# main.net
KiCad netlist of a schematic drawn in Altium Designer
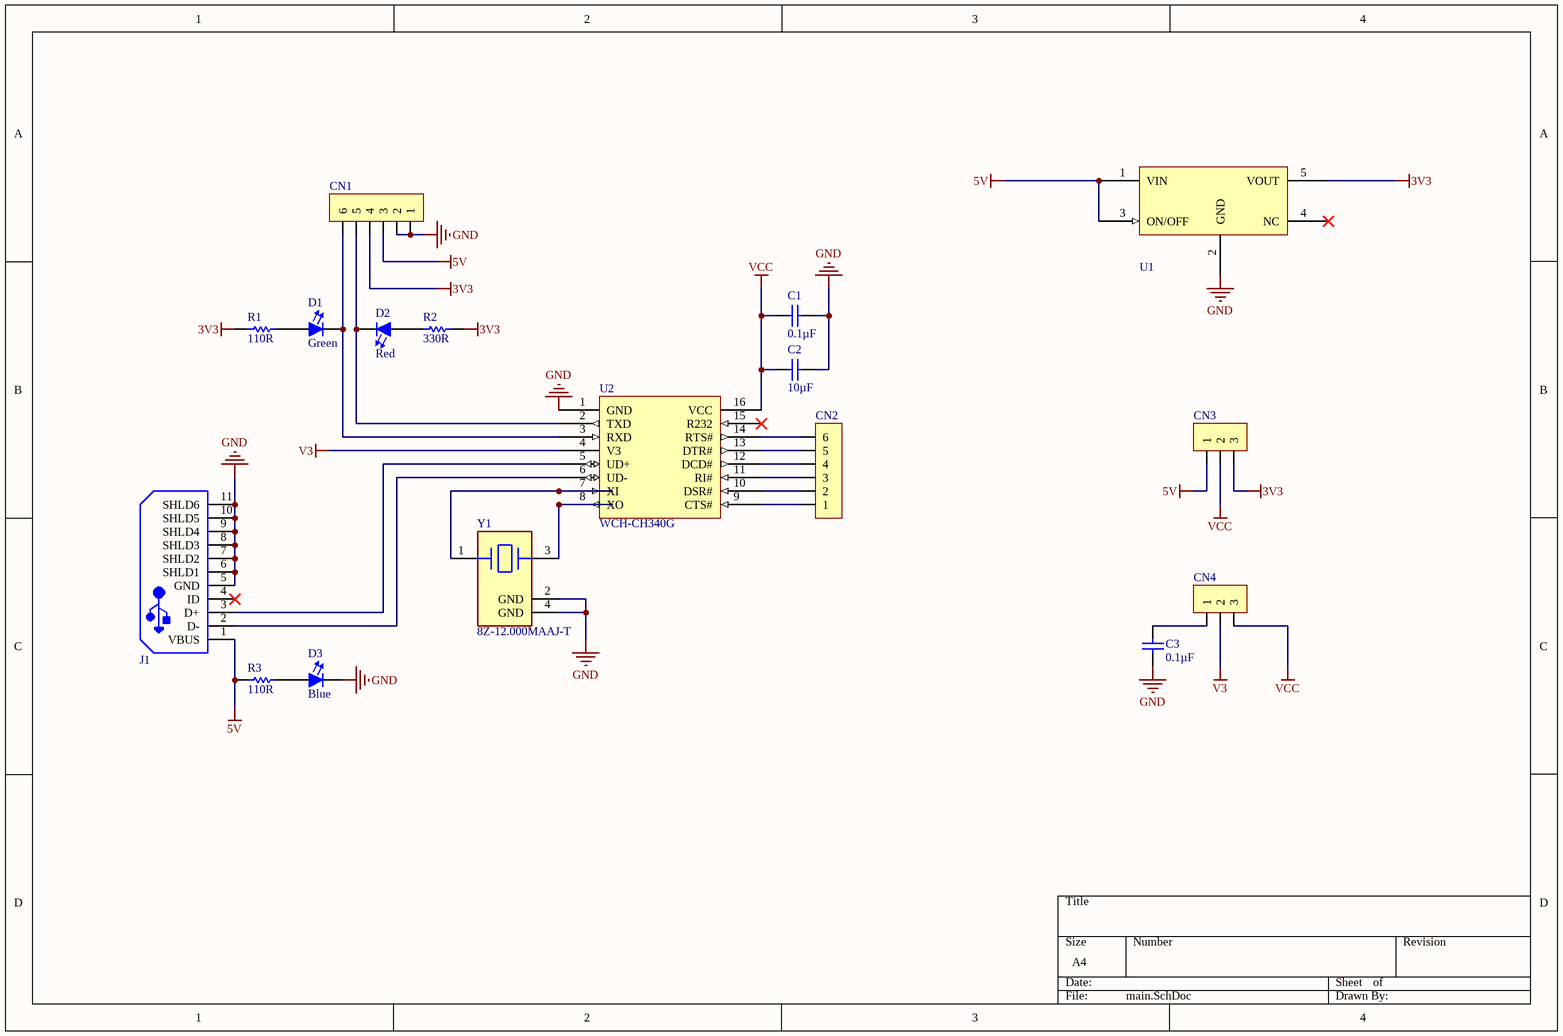
[diagram p0: main.SchDoc]

(export (version "E")
  (design (tool "Eeschema 10.0.6"))
  (components
    (comp (ref "C1")
      (value "0.1µF")
      (footprint "CAPC1608N(0603\")")
      (description "Capacitor, Ceramic, 16V, +/- 10%, 0603 SMD, X7R")
      (fields
        (field (name "Comment") "0.1uF 16V 0603 SMD, Ceramic")
        (field (name "CREATED BY") "Andy Bates")
        (field (name "SOURCE") "AUVic_Schematic_Library_Capacitors.SchLib")
        (field (name "PUBLISHER") "AUVic")
      )
      (libsource (lib "") (part "Symbol_1"))
    )
    (comp (ref "C2")
      (value "10µF")
      (footprint "CAPC1608N(0603\")")
      (description "Capacitor, Ceramic, 16V, +/- 10%, 0603 SMD, X7R")
      (fields
        (field (name "Comment") "0.1uF 16V 0603 SMD, Ceramic")
        (field (name "CREATED BY") "Andy Bates")
        (field (name "SOURCE") "AUVic_Schematic_Library_Capacitors.SchLib")
        (field (name "PUBLISHER") "AUVic")
      )
      (libsource (lib "") (part "Symbol_1"))
    )
    (comp (ref "C3")
      (value "0.1µF")
      (footprint "CAPC1608N(0603\")")
      (description "Capacitor, Ceramic, 16V, +/- 10%, 0603 SMD, X7R")
      (fields
        (field (name "Comment") "0.1uF 16V 0603 SMD, Ceramic")
        (field (name "CREATED BY") "Andy Bates")
        (field (name "SOURCE") "AUVic_Schematic_Library_Capacitors.SchLib")
        (field (name "PUBLISHER") "AUVic")
      )
      (libsource (lib "") (part "Symbol_1"))
    )
    (comp (ref "CN1")
      (value "Header, Male, 1x6")
      (footprint "Header, Male, 1X6")
      (description "1x6, Pads Pitch: 0.1\" (2.54mm), Through hole")
      (fields (field (name "SOURCE") "AUVic_Schematic_Library_Connectors.SchLib"))
      (libsource (lib "") (part "Symbol_3"))
    )
    (comp (ref "CN2")
      (value "Header, Male, 1x6")
      (footprint "Header, Male, 1X6")
      (description "1x6, Pads Pitch: 0.1\" (2.54mm), Through hole")
      (fields (field (name "SOURCE") "AUVic_Schematic_Library_Connectors.SchLib"))
      (libsource (lib "") (part "Symbol_4"))
    )
    (comp (ref "CN3")
      (value "Header, Male, 1x3, Pitch: 0.1\" (2.54mm), THT")
      (footprint "Header, Male, 1x3, Pitch: 0.1\" (2.54mm),THT")
      (fields
        (field (name "CREATED BY") "Ashwin Sira")
        (field (name "REVIEWED BY") "*")
        (field (name "SOURCE") "AUVic_Schematic_Library_Connectors.SchLib")
        (field (name "PUBLISHER") "AUVic")
      )
      (libsource (lib "") (part "Symbol_2"))
    )
    (comp (ref "CN4")
      (value "Header, Male, 1x3, Pitch: 0.1\" (2.54mm), THT")
      (footprint "Header, Male, 1x3, Pitch: 0.1\" (2.54mm),THT")
      (fields
        (field (name "CREATED BY") "Ashwin Sira")
        (field (name "REVIEWED BY") "*")
        (field (name "SOURCE") "AUVic_Schematic_Library_Connectors.SchLib")
        (field (name "PUBLISHER") "AUVic")
      )
      (libsource (lib "") (part "Symbol_2"))
    )
    (comp (ref "D1")
      (value "LT Q39G-Q1OO-25-1")
      (footprint "FP-LB_Q39E-MFG")
      (description "LED GREEN DIFFUSED 0603 SMD")
      (fields (field (name "COLOR") "Green"))
      (libsource (lib "AUVIC") (part "Symbol"))
    )
    (comp (ref "D2")
      (value "LSQ976-NR-1")
      (footprint "FP-LB_Q39E-MFG")
      (description "LED Red 645nm 2-Pin Chip 0603(1608Metric) T/R")
      (fields (field (name "COLOR") "Red"))
      (libsource (lib "AUVIC") (part "Symbol"))
    )
    (comp (ref "D3")
      (value "LBQ39E-N1OO-35-1")
      (footprint "FP-LB_Q39E-MFG")
      (description "LED BLUE DIFFUSED 0603 SMD")
      (fields (field (name "COLOR") "Blue"))
      (libsource (lib "AUVIC") (part "Symbol"))
    )
    (comp (ref "J1")
      (value "10118192-0002LF")
      (footprint "FCI-10118192-0001LF-5_V")
      (description "CONN RCPT USB2.0 MICRO B SMD R/A")
      (fields (field (name "DK PART NUMBER") "609-5379-1-ND"))
      (libsource (lib "AUVIC") (part "USB-5-6SHLD"))
    )
    (comp (ref "R1")
      (value "RC0603FR-07110RL")
      (footprint "RESC1608X55X25ML10T15")
      (description "RES SMD 110 OHM 1% 1/10W 0603")
      (fields (field (name "TOLERANCE") "1%") (field (name "RESISTANCE") "110R"))
      (libsource (lib "AUVIC") (part "RES"))
    )
    (comp (ref "R2")
      (value "RK73B1JTTD331J")
      (footprint "RESC1608X55X30LL20T10")
      (description "Res Thick Film 0603 330 Ohm 5% 0.1W(1/10W) ±200ppm/C Molded SMD Automotive T/R")
      (fields (field (name "TOLERANCE") "5%") (field (name "RESISTANCE") "330R"))
      (libsource (lib "AUVIC") (part "RES"))
    )
    (comp (ref "R3")
      (value "RC0603FR-07110RL")
      (footprint "RESC1608X55X25ML10T15")
      (description "RES SMD 110 OHM 1% 1/10W 0603")
      (fields (field (name "TOLERANCE") "1%") (field (name "RESISTANCE") "110R"))
      (libsource (lib "AUVIC") (part "RES"))
    )
    (comp (ref "U1")
      (value "LP2981-33DBVR")
      (footprint "SOT95P280X145-5N")
      (description "IC REG LINEAR 3.3V 100MA SOT23-5")
      (libsource (lib "AUVIC") (part "LP2981-33DBVR"))
    )
    (comp (ref "U2")
      (value "WCH-CH340G")
      (footprint "SOP127P600X175-16N")
      (description "USB to UART Transceiver. USB 2.0 2Mbps. LCSC #C14267")
      (fields (field (name "LCSC PART NUMBER") "C14267"))
      (libsource (lib "AUVIC") (part "WCH-CH340G"))
    )
    (comp (ref "Y1")
      (value "8Z-12.000MAAJ-T")
      (footprint "FP-8Z-MFG")
      (description "CRYSTAL 12.0000MHZ 18PF SMD")
      (fields (field (name "TOLERANCE") "30ppm"))
      (libsource (lib "Altium Content Vault") (part "82e0a36ce47690002882b131d1ef993"))
    )
  )
  (nets
    (net (code "1") (name "3V3") (class "Default")
      (node (ref "CN1") (pin "4") (pinfunction "4_4") (pintype "passive"))
      (node (ref "CN3") (pin "3") (pinfunction "3_3") (pintype "passive"))
      (node (ref "R1") (pin "2") (pinfunction "2_2") (pintype "passive"))
      (node (ref "R2") (pin "2") (pinfunction "2_2") (pintype "passive"))
      (node (ref "U1") (pin "5") (pinfunction "VOUT_5") (pintype "power_in"))
    )
    (net (code "2") (name "5V") (class "Default")
      (node (ref "CN1") (pin "3") (pinfunction "3_3") (pintype "passive"))
      (node (ref "CN3") (pin "1") (pinfunction "1_1") (pintype "passive"))
      (node (ref "J1") (pin "1") (pinfunction "VBUS_1") (pintype "passive"))
      (node (ref "R3") (pin "2") (pinfunction "2_2") (pintype "passive"))
      (node (ref "U1") (pin "1") (pinfunction "VIN_1") (pintype "power_in"))
      (node (ref "U1") (pin "3") (pinfunction "ON/OFF_3") (pintype "input"))
    )
    (net (code "3") (name "GND") (class "Default")
      (node (ref "C1") (pin "2") (pinfunction "Cathode_2") (pintype "passive"))
      (node (ref "C2") (pin "2") (pinfunction "Cathode_2") (pintype "passive"))
      (node (ref "C3") (pin "1") (pinfunction "Anode_1") (pintype "passive"))
      (node (ref "CN1") (pin "1") (pinfunction "1_1") (pintype "passive"))
      (node (ref "CN1") (pin "2") (pinfunction "2_2") (pintype "passive"))
      (node (ref "D3") (pin "1") (pinfunction "Cathode_1") (pintype "passive"))
      (node (ref "J1") (pin "10") (pinfunction "SHLD5_10") (pintype "passive"))
      (node (ref "J1") (pin "11") (pinfunction "SHLD6_11") (pintype "passive"))
      (node (ref "J1") (pin "5") (pinfunction "GND_5") (pintype "passive"))
      (node (ref "J1") (pin "6") (pinfunction "SHLD1_6") (pintype "passive"))
      (node (ref "J1") (pin "7") (pinfunction "SHLD2_7") (pintype "passive"))
      (node (ref "J1") (pin "8") (pinfunction "SHLD3_8") (pintype "passive"))
      (node (ref "J1") (pin "9") (pinfunction "SHLD4_9") (pintype "passive"))
      (node (ref "U1") (pin "2") (pinfunction "GND_2") (pintype "power_in"))
      (node (ref "U2") (pin "1") (pinfunction "GND_1") (pintype "power_in"))
      (node (ref "Y1") (pin "2") (pinfunction "GND_2") (pintype "power_in"))
      (node (ref "Y1") (pin "4") (pinfunction "GND_4") (pintype "power_in"))
    )
    (net (code "4") (name "Net-(C3-Cathode)") (class "Default")
      (node (ref "C3") (pin "2") (pinfunction "Cathode_2") (pintype "passive"))
      (node (ref "CN4") (pin "1") (pinfunction "1_1") (pintype "passive"))
    )
    (net (code "5") (name "Net-(D1-Anode)") (class "Default")
      (node (ref "D1") (pin "2") (pinfunction "Anode_2") (pintype "passive"))
      (node (ref "R1") (pin "1") (pinfunction "1_1") (pintype "passive"))
    )
    (net (code "6") (name "Net-(D1-Cathode)") (class "Default")
      (node (ref "CN1") (pin "6") (pinfunction "6_6") (pintype "passive"))
      (node (ref "D1") (pin "1") (pinfunction "Cathode_1") (pintype "passive"))
      (node (ref "U2") (pin "3") (pinfunction "RXD_3") (pintype "input"))
    )
    (net (code "7") (name "Net-(D2-Anode)") (class "Default")
      (node (ref "D2") (pin "2") (pinfunction "Anode_2") (pintype "passive"))
      (node (ref "R2") (pin "1") (pinfunction "1_1") (pintype "passive"))
    )
    (net (code "8") (name "Net-(D2-Cathode)") (class "Default")
      (node (ref "CN1") (pin "5") (pinfunction "5_5") (pintype "passive"))
      (node (ref "D2") (pin "1") (pinfunction "Cathode_1") (pintype "passive"))
      (node (ref "U2") (pin "2") (pinfunction "TXD_2") (pintype "output"))
    )
    (net (code "9") (name "Net-(D3-Anode)") (class "Default")
      (node (ref "D3") (pin "2") (pinfunction "Anode_2") (pintype "passive"))
      (node (ref "R3") (pin "1") (pinfunction "1_1") (pintype "passive"))
    )
    (net (code "10") (name "Net-(J1-D+)") (class "Default")
      (node (ref "J1") (pin "3") (pinfunction "D+_3") (pintype "passive"))
      (node (ref "U2") (pin "5") (pinfunction "UD+_5") (pintype "bidirectional"))
    )
    (net (code "11") (name "Net-(J1-D-)") (class "Default")
      (node (ref "J1") (pin "2") (pinfunction "D-_2") (pintype "passive"))
      (node (ref "U2") (pin "6") (pinfunction "UD-_6") (pintype "bidirectional"))
    )
    (net (code "12") (name "Net-(U2-CTS#)") (class "Default")
      (node (ref "CN2") (pin "1") (pinfunction "1_1") (pintype "passive"))
      (node (ref "U2") (pin "9") (pinfunction "CTS#_9") (pintype "input"))
    )
    (net (code "13") (name "Net-(U2-DCD#)") (class "Default")
      (node (ref "CN2") (pin "4") (pinfunction "4_4") (pintype "passive"))
      (node (ref "U2") (pin "12") (pinfunction "DCD#_12") (pintype "output"))
    )
    (net (code "14") (name "Net-(U2-DSR#)") (class "Default")
      (node (ref "CN2") (pin "2") (pinfunction "2_2") (pintype "passive"))
      (node (ref "U2") (pin "10") (pinfunction "DSR#_10") (pintype "input"))
    )
    (net (code "15") (name "Net-(U2-DTR#)") (class "Default")
      (node (ref "CN2") (pin "5") (pinfunction "5_5") (pintype "passive"))
      (node (ref "U2") (pin "13") (pinfunction "DTR#_13") (pintype "output"))
    )
    (net (code "16") (name "Net-(U2-RI#)") (class "Default")
      (node (ref "CN2") (pin "3") (pinfunction "3_3") (pintype "passive"))
      (node (ref "U2") (pin "11") (pinfunction "RI#_11") (pintype "input"))
    )
    (net (code "17") (name "Net-(U2-RTS#)") (class "Default")
      (node (ref "CN2") (pin "6") (pinfunction "6_6") (pintype "passive"))
      (node (ref "U2") (pin "14") (pinfunction "RTS#_14") (pintype "output"))
    )
    (net (code "18") (name "Net-(U2-XI)") (class "Default")
      (node (ref "U2") (pin "7") (pinfunction "XI_7") (pintype "input"))
      (node (ref "Y1") (pin "1") (pinfunction "1_1") (pintype "passive"))
    )
    (net (code "19") (name "Net-(U2-XO)") (class "Default")
      (node (ref "U2") (pin "8") (pinfunction "XO_8") (pintype "output"))
      (node (ref "Y1") (pin "3") (pinfunction "3_3") (pintype "passive"))
    )
    (net (code "20") (name "V3") (class "Default")
      (node (ref "CN4") (pin "2") (pinfunction "2_2") (pintype "passive"))
      (node (ref "U2") (pin "4") (pinfunction "V3_4") (pintype "power_in"))
    )
    (net (code "21") (name "VCC") (class "Default")
      (node (ref "C1") (pin "1") (pinfunction "Anode_1") (pintype "passive"))
      (node (ref "C2") (pin "1") (pinfunction "Anode_1") (pintype "passive"))
      (node (ref "CN3") (pin "2") (pinfunction "2_2") (pintype "passive"))
      (node (ref "CN4") (pin "3") (pinfunction "3_3") (pintype "passive"))
      (node (ref "U2") (pin "16") (pinfunction "VCC_16") (pintype "power_in"))
    )
    (net (code "22") (name "unconnected-(J1-ID-Pad4)") (class "Default")
      (node (ref "J1") (pin "4") (pinfunction "ID_4") (pintype "passive+no_connect"))
    )
    (net (code "23") (name "unconnected-(U1-NC-Pad4)") (class "Default")
      (node (ref "U1") (pin "4") (pinfunction "NC_4") (pintype "passive+no_connect"))
    )
    (net (code "24") (name "unconnected-(U2-R232-Pad15)") (class "Default")
      (node (ref "U2") (pin "15") (pinfunction "R232_15") (pintype "input+no_connect"))
    )
  )
)
